# Master_MicroController_Core.net
KiCad netlist of a schematic drawn in Altium Designer
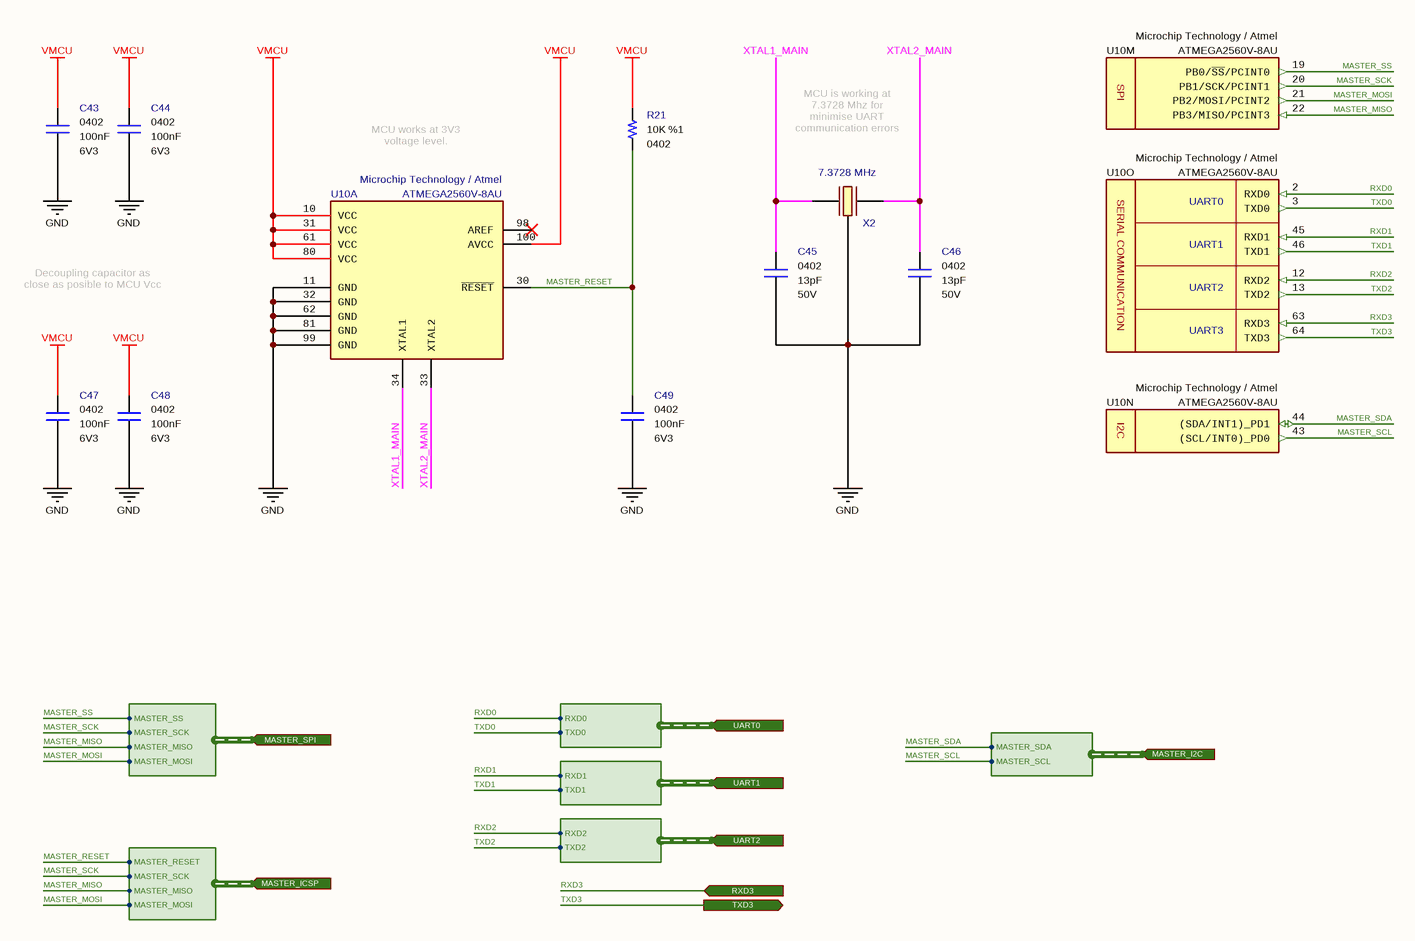
[diagram p0: Master MicroController Core.SchDoc]

(export (version "E")
  (design (tool "Eeschema 10.0.6"))
  (components
    (comp (ref "C43")
      (value "100nF")
      (footprint "CAPACITOR_0402")
      (description "Capacitor - 100nF [0402-6V3] (Ceramic)")
      (fields
        (field (name "TOLERANCE") "%10")
        (field (name "CASE") "0402")
        (field (name "VOLTAGE") "6V3")
        (field (name "MANUFACTURER PART NUMBER") "04026D104KAT4A")
      )
      (libsource (lib "Ovoo_Library") (part "Capacitor - 100nF [0402-6V3]"))
    )
    (comp (ref "C44")
      (value "100nF")
      (footprint "CAPACITOR_0402")
      (description "Capacitor - 100nF [0402-6V3] (Ceramic)")
      (fields
        (field (name "TOLERANCE") "%10")
        (field (name "CASE") "0402")
        (field (name "VOLTAGE") "6V3")
        (field (name "MANUFACTURER PART NUMBER") "04026D104KAT4A")
      )
      (libsource (lib "Ovoo_Library") (part "Capacitor - 100nF [0402-6V3]"))
    )
    (comp (ref "C45")
      (value "13pF")
      (footprint "CAPACITOR_0402")
      (description "Capacitor - 13pF [0402] (Ceramic)")
      (fields
        (field (name "TOLERANCE") "1%")
        (field (name "VOLTAGE") "50V")
        (field (name "CASE") "0402")
        (field (name "MANUFACTURER PART NUMBER") "CBR04C130F5GAC")
      )
      (libsource (lib "Ovoo_Library") (part "Capacitor - 13pF [0402-50V]"))
    )
    (comp (ref "C46")
      (value "13pF")
      (footprint "CAPACITOR_0402")
      (description "Capacitor - 13pF [0402] (Ceramic)")
      (fields
        (field (name "TOLERANCE") "1%")
        (field (name "VOLTAGE") "50V")
        (field (name "CASE") "0402")
        (field (name "MANUFACTURER PART NUMBER") "CBR04C130F5GAC")
      )
      (libsource (lib "Ovoo_Library") (part "Capacitor - 13pF [0402-50V]"))
    )
    (comp (ref "C47")
      (value "100nF")
      (footprint "CAPACITOR_0402")
      (description "Capacitor - 100nF [0402-6V3] (Ceramic)")
      (fields
        (field (name "TOLERANCE") "%10")
        (field (name "CASE") "0402")
        (field (name "VOLTAGE") "6V3")
        (field (name "MANUFACTURER PART NUMBER") "04026D104KAT4A")
      )
      (libsource (lib "Ovoo_Library") (part "Capacitor - 100nF [0402-6V3]"))
    )
    (comp (ref "C48")
      (value "100nF")
      (footprint "CAPACITOR_0402")
      (description "Capacitor - 100nF [0402-6V3] (Ceramic)")
      (fields
        (field (name "TOLERANCE") "%10")
        (field (name "CASE") "0402")
        (field (name "VOLTAGE") "6V3")
        (field (name "MANUFACTURER PART NUMBER") "04026D104KAT4A")
      )
      (libsource (lib "Ovoo_Library") (part "Capacitor - 100nF [0402-6V3]"))
    )
    (comp (ref "C49")
      (value "100nF")
      (footprint "CAPACITOR_0402")
      (description "Capacitor - 100nF [0402-6V3] (Ceramic)")
      (fields
        (field (name "TOLERANCE") "%10")
        (field (name "CASE") "0402")
        (field (name "VOLTAGE") "6V3")
        (field (name "MANUFACTURER PART NUMBER") "04026D104KAT4A")
      )
      (libsource (lib "Ovoo_Library") (part "Capacitor - 100nF [0402-6V3]"))
    )
    (comp (ref "R21")
      (value "10K")
      (footprint "RESISTOR_0402")
      (description "Thick Film Resistors - SMD 1/16 W 10 Kohms 1%")
      (fields
        (field (name "TOLERANCE") "%1")
        (field (name "CASE") "0402")
        (field (name "MANUFACTURER PART NUMBER") "CRCW040210K0FKED")
        (field (name "MOUSER PART NUMBER") "71-CRCW0402-10K-E3")
      )
      (libsource (lib "Ovoo_Library") (part "Resistor - 10K"))
    )
    (comp (ref "U10")
      (value "8-bit MicroController")
      (footprint "TQFP100")
      (description "8-bit Microcontrollers - MCU 256kB Flash 4kB EEPROM 86 I/O Pins")
      (fields
        (field (name "MOUSER_PART_NUMBER") "556-ATMEGA2560V8AU")
        (field (name "MANUFACTURER_PART_NUMBER") "ATMEGA2560V-8AU")
        (field (name "MANUFACTURER_NAME") "Microchip Technology / Atmel")
        (field (name "MANUFACTURER PART NUMBER") "ATMEGA2560V-8AU")
        (field (name "MANUFACTURER NAME") "Microchip Technology / Atmel")
      )
      (libsource (lib "Ovoo_Library") (part "IC - ATMEGA2560V-8AU"))
    )
    (comp (ref "X2")
      (value "7.3728 MHz")
      (footprint "ABRACON_CRYSTAL")
      (description "Crystals 7.3728MHz 18pF -40C +85C")
      (fields
        (field (name "MANUFACTURER PART NUMBER") "ABMM2-7.3728MHZ-E2-T")
        (field (name "MOUSER PART NUMBER") "815-ABMM2-7.3-E2-T")
      )
      (libsource (lib "Ovoo_Library") (part "Crystal - 7.3728 MHz (Abracon)"))
    )
  )
  (nets
    (net (code "7") (name "/MASTER_MISO") (class "Default")
      (node (ref "U10") (pin "22") (pinfunction "PB3/MISO/PCINT3_22") (pintype "passive"))
    )
    (net (code "8") (name "/MASTER_MOSI") (class "Default")
      (node (ref "U10") (pin "21") (pinfunction "PB2/MOSI/PCINT2_21") (pintype "passive"))
    )
    (net (code "9") (name "/MASTER_RESET") (class "Default")
      (node (ref "C49") (pin "2") (pinfunction "2_2") (pintype "passive"))
      (node (ref "R21") (pin "1") (pinfunction "1_1") (pintype "passive"))
      (node (ref "U10") (pin "30") (pinfunction "~{RESET}_30") (pintype "passive"))
    )
    (net (code "10") (name "/MASTER_SCK") (class "Default")
      (node (ref "U10") (pin "20") (pinfunction "PB1/SCK/PCINT1_20") (pintype "passive"))
    )
    (net (code "11") (name "/MASTER_SCL") (class "Default")
      (node (ref "U10") (pin "43") (pinfunction "(SCL/INT0)_PD0_43") (pintype "passive"))
    )
    (net (code "12") (name "/MASTER_SDA") (class "Default")
      (node (ref "U10") (pin "44") (pinfunction "(SDA/INT1)_PD1_44") (pintype "passive"))
    )
    (net (code "13") (name "/MASTER_SS") (class "Default")
      (node (ref "U10") (pin "19") (pinfunction "PB0/~{SS}/PCINT0_19") (pintype "passive"))
    )
    (net (code "14") (name "/RXD0") (class "Default")
      (node (ref "U10") (pin "2") (pinfunction "RXD0_2") (pintype "input"))
    )
    (net (code "15") (name "/RXD1") (class "Default")
      (node (ref "U10") (pin "45") (pinfunction "RXD1_45") (pintype "input"))
    )
    (net (code "16") (name "/RXD2") (class "Default")
      (node (ref "U10") (pin "12") (pinfunction "RXD2_12") (pintype "input"))
    )
    (net (code "17") (name "/RXD3") (class "Default")
      (node (ref "U10") (pin "63") (pinfunction "RXD3_63") (pintype "input"))
    )
    (net (code "18") (name "/TXD0") (class "Default")
      (node (ref "U10") (pin "3") (pinfunction "TXD0_3") (pintype "output"))
    )
    (net (code "19") (name "/TXD1") (class "Default")
      (node (ref "U10") (pin "46") (pinfunction "TXD1_46") (pintype "output"))
    )
    (net (code "20") (name "/TXD2") (class "Default")
      (node (ref "U10") (pin "13") (pinfunction "TXD2_13") (pintype "output"))
    )
    (net (code "21") (name "/TXD3") (class "Default")
      (node (ref "U10") (pin "64") (pinfunction "TXD3_64") (pintype "output"))
    )
    (net (code "22") (name "/XTAL1_MAIN") (class "Default")
      (node (ref "C45") (pin "2") (pinfunction "2_2") (pintype "passive"))
      (node (ref "U10") (pin "34") (pinfunction "XTAL1_34") (pintype "passive"))
      (node (ref "X2") (pin "3") (pinfunction "OUT/IN_3") (pintype "passive"))
    )
    (net (code "23") (name "/XTAL2_MAIN") (class "Default")
      (node (ref "C46") (pin "2") (pinfunction "2_2") (pintype "passive"))
      (node (ref "U10") (pin "33") (pinfunction "XTAL2_33") (pintype "passive"))
      (node (ref "X2") (pin "1") (pinfunction "IN/OUT_1") (pintype "passive"))
    )
    (net (code "30") (name "GND") (class "Default")
      (node (ref "C43") (pin "1") (pinfunction "1_1") (pintype "passive"))
      (node (ref "C44") (pin "1") (pinfunction "1_1") (pintype "passive"))
      (node (ref "C45") (pin "1") (pinfunction "1_1") (pintype "passive"))
      (node (ref "C46") (pin "1") (pinfunction "1_1") (pintype "passive"))
      (node (ref "C47") (pin "1") (pinfunction "1_1") (pintype "passive"))
      (node (ref "C48") (pin "1") (pinfunction "1_1") (pintype "passive"))
      (node (ref "C49") (pin "1") (pinfunction "1_1") (pintype "passive"))
      (node (ref "U10") (pin "11") (pinfunction "GND_11") (pintype "passive"))
      (node (ref "U10") (pin "32") (pinfunction "GND_32") (pintype "passive"))
      (node (ref "U10") (pin "62") (pinfunction "GND_62") (pintype "passive"))
      (node (ref "U10") (pin "81") (pinfunction "GND_81") (pintype "passive"))
      (node (ref "U10") (pin "99") (pinfunction "GND_99") (pintype "passive"))
      (node (ref "X2") (pin "2") (pinfunction "GND_2") (pintype "passive"))
    )
    (net (code "31") (name "VMCU") (class "Default")
      (node (ref "C43") (pin "2") (pinfunction "2_2") (pintype "passive"))
      (node (ref "C44") (pin "2") (pinfunction "2_2") (pintype "passive"))
      (node (ref "C47") (pin "2") (pinfunction "2_2") (pintype "passive"))
      (node (ref "C48") (pin "2") (pinfunction "2_2") (pintype "passive"))
      (node (ref "R21") (pin "2") (pinfunction "2_2") (pintype "passive"))
      (node (ref "U10") (pin "10") (pinfunction "VCC_10") (pintype "power_in"))
      (node (ref "U10") (pin "100") (pinfunction "AVCC_100") (pintype "passive"))
      (node (ref "U10") (pin "31") (pinfunction "VCC_31") (pintype "power_in"))
      (node (ref "U10") (pin "61") (pinfunction "VCC_61") (pintype "power_in"))
      (node (ref "U10") (pin "80") (pinfunction "VCC_80") (pintype "power_in"))
    )
    (net (code "32") (name "unconnected-(U10A-AREF-Pad98)") (class "Default")
      (node (ref "U10") (pin "98") (pinfunction "AREF_98") (pintype "passive+no_connect"))
    )
    (net (code "33") (name "unconnected-(X2-GND-Pad4)") (class "Default")
      (node (ref "X2") (pin "4") (pinfunction "GND_4") (pintype "passive"))
    )
  )
)
